# Microcontroller.net
KiCad netlist of a schematic drawn in Altium Designer
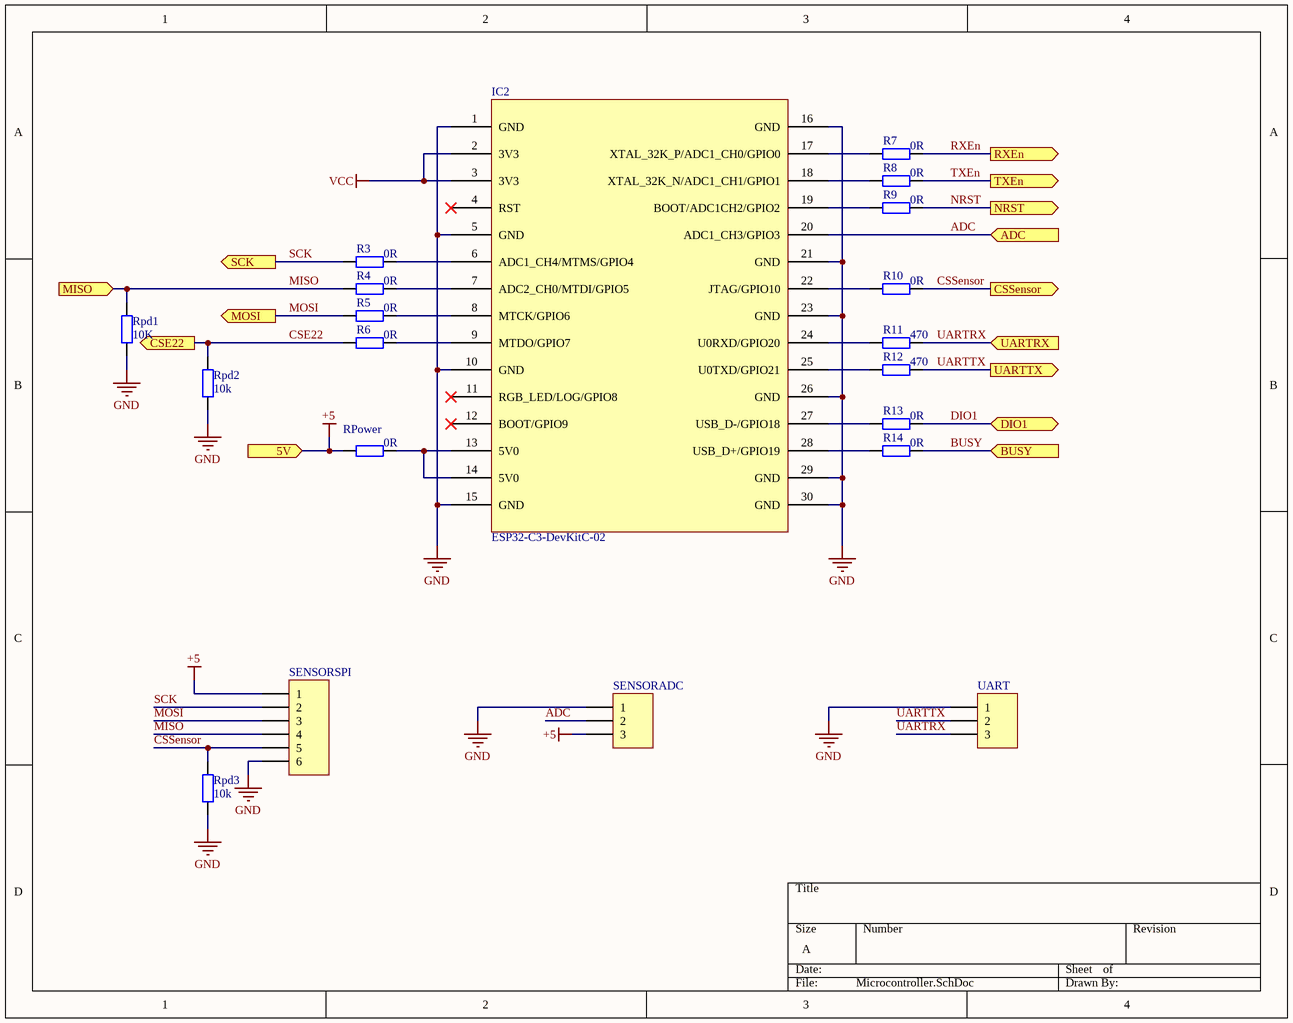
[diagram p0: Microcontroller.SchDoc]

(export (version "E")
  (design (tool "Eeschema 10.0.6"))
  (components
    (comp (ref "IC2")
      (value "ESP32-C3-DevKitC-02")
      (footprint "ESP32-C3-DevKitC-02")
      (libsource (lib "ESP32-C3-DevKitC-02") (part "ESP32-C3-DevKitC-02"))
    )
    (comp (ref "R3")
      (value "0R")
      (footprint "RES0805")
      (description "Resistor")
      (fields
        (field (name "LCSC PART #") "C2074219")
        (field (name "Comment") "Res2")
        (field (name "PUBLISHER") "Altium Limited")
      )
      (libsource (lib "Miscellaneous Devices") (part "Res2"))
    )
    (comp (ref "R4")
      (value "0R")
      (footprint "RES0805")
      (description "Resistor")
      (fields
        (field (name "LCSC PART #") "C2074219")
        (field (name "Comment") "Res2")
        (field (name "PUBLISHER") "Altium Limited")
      )
      (libsource (lib "Miscellaneous Devices") (part "Res2"))
    )
    (comp (ref "R5")
      (value "0R")
      (footprint "RES0805")
      (description "Resistor")
      (fields
        (field (name "LCSC PART #") "C2074219")
        (field (name "Comment") "Res2")
        (field (name "PUBLISHER") "Altium Limited")
      )
      (libsource (lib "Miscellaneous Devices") (part "Res2"))
    )
    (comp (ref "R6")
      (value "0R")
      (footprint "RES0805")
      (description "Resistor")
      (fields
        (field (name "LCSC PART #") "C2074219")
        (field (name "Comment") "Res2")
        (field (name "PUBLISHER") "Altium Limited")
      )
      (libsource (lib "Miscellaneous Devices") (part "Res2"))
    )
    (comp (ref "R7")
      (value "0R")
      (footprint "RES0805")
      (description "Resistor")
      (fields
        (field (name "LCSC PART #") "C2074219")
        (field (name "Comment") "Res2")
        (field (name "PUBLISHER") "Altium Limited")
      )
      (libsource (lib "Miscellaneous Devices") (part "Res2"))
    )
    (comp (ref "R8")
      (value "0R")
      (footprint "RES0805")
      (description "Resistor")
      (fields
        (field (name "LCSC PART #") "C2074219")
        (field (name "Comment") "Res2")
        (field (name "PUBLISHER") "Altium Limited")
      )
      (libsource (lib "Miscellaneous Devices") (part "Res2"))
    )
    (comp (ref "R9")
      (value "0R")
      (footprint "RES0805")
      (description "Resistor")
      (fields
        (field (name "LCSC PART #") "C2074219")
        (field (name "Comment") "Res2")
        (field (name "PUBLISHER") "Altium Limited")
      )
      (libsource (lib "Miscellaneous Devices") (part "Res2"))
    )
    (comp (ref "R10")
      (value "0R")
      (footprint "RES0805")
      (description "Resistor")
      (fields
        (field (name "LCSC PART #") "C2074219")
        (field (name "Comment") "Res2")
        (field (name "PUBLISHER") "Altium Limited")
      )
      (libsource (lib "Miscellaneous Devices") (part "Res2"))
    )
    (comp (ref "R11")
      (value "470")
      (footprint "RES0805")
      (description "Resistor")
      (fields
        (field (name "LCSC PART #") "C2074219")
        (field (name "Comment") "Res2")
        (field (name "PUBLISHER") "Altium Limited")
      )
      (libsource (lib "Miscellaneous Devices") (part "Res2"))
    )
    (comp (ref "R12")
      (value "470")
      (footprint "RES0805")
      (description "Resistor")
      (fields
        (field (name "LCSC PART #") "C2074219")
        (field (name "Comment") "Res2")
        (field (name "PUBLISHER") "Altium Limited")
      )
      (libsource (lib "Miscellaneous Devices") (part "Res2"))
    )
    (comp (ref "R13")
      (value "0R")
      (footprint "RES0805")
      (description "Resistor")
      (fields
        (field (name "LCSC PART #") "C2074219")
        (field (name "Comment") "Res2")
        (field (name "PUBLISHER") "Altium Limited")
      )
      (libsource (lib "Miscellaneous Devices") (part "Res2"))
    )
    (comp (ref "R14")
      (value "0R")
      (footprint "RES0805")
      (description "Resistor")
      (fields
        (field (name "LCSC PART #") "C2074219")
        (field (name "Comment") "Res2")
        (field (name "PUBLISHER") "Altium Limited")
      )
      (libsource (lib "Miscellaneous Devices") (part "Res2"))
    )
    (comp (ref "Rpd1")
      (value "10K")
      (footprint "RES0805")
      (description "Resistor")
      (fields
        (field (name "LCSC PART #") "C2074219")
        (field (name "Comment") "Res2")
        (field (name "PUBLISHER") "Altium Limited")
      )
      (libsource (lib "") (part "Res2_1"))
    )
    (comp (ref "Rpd2")
      (value "10k")
      (footprint "RES0805")
      (description "Resistor")
      (fields
        (field (name "LCSC PART #") "C2074219")
        (field (name "Comment") "Res2")
        (field (name "PUBLISHER") "Altium Limited")
      )
      (libsource (lib "") (part "Res2_1"))
    )
    (comp (ref "Rpd3")
      (value "10k")
      (footprint "RES0805")
      (description "Resistor")
      (fields
        (field (name "LCSC PART #") "C2074219")
        (field (name "Comment") "Res2")
        (field (name "PUBLISHER") "Altium Limited")
      )
      (libsource (lib "") (part "Res2_1"))
    )
    (comp (ref "RPower")
      (value "0R")
      (footprint "RES0805")
      (description "Resistor")
      (fields
        (field (name "LCSC PART #") "C2074219")
        (field (name "Comment") "Res2")
        (field (name "PUBLISHER") "Altium Limited")
      )
      (libsource (lib "Miscellaneous Devices") (part "Res2"))
    )
    (comp (ref "SENSORADC")
      (value "Header 3")
      (footprint "Conn 1x3P")
      (description "Header, 3-Pin")
      (fields (field (name "PUBLISHER") "Altium Limited"))
      (libsource (lib "Miscellaneous Connectors") (part "Header 3"))
    )
    (comp (ref "SENSORSPI")
      (value "Header 6")
      (footprint "Conn 1x6P")
      (description "Header, 6-Pin")
      (fields (field (name "PUBLISHER") "Altium Limited"))
      (libsource (lib "Miscellaneous Connectors") (part "Header 6"))
    )
    (comp (ref "UART")
      (value "Header 3")
      (footprint "Conn 1x3P")
      (description "Header, 3-Pin")
      (fields (field (name "PUBLISHER") "Altium Limited"))
      (libsource (lib "Miscellaneous Connectors") (part "Header 3"))
    )
  )
  (nets
    (net (code "1") (name "+5") (class "Default")
      (node (ref "RPower") (pin "1") (pinfunction "1_1") (pintype "passive"))
      (node (ref "SENSORADC") (pin "3") (pinfunction "3_3") (pintype "passive"))
      (node (ref "SENSORSPI") (pin "1") (pinfunction "1_1") (pintype "passive"))
    )
    (net (code "2") (name "/ADC") (class "Default")
      (node (ref "IC2") (pin "20") (pinfunction "ADC1_CH3/GPIO3_20") (pintype "passive"))
      (node (ref "SENSORADC") (pin "2") (pinfunction "2_2") (pintype "passive"))
    )
    (net (code "3") (name "/BUSY") (class "Default")
      (node (ref "R14") (pin "2") (pinfunction "2_2") (pintype "passive"))
    )
    (net (code "4") (name "/CSE22") (class "Default")
      (node (ref "R6") (pin "1") (pinfunction "1_1") (pintype "passive"))
      (node (ref "Rpd2") (pin "2") (pinfunction "2_2") (pintype "passive"))
    )
    (net (code "5") (name "/CSSensor") (class "Default")
      (node (ref "R10") (pin "2") (pinfunction "2_2") (pintype "passive"))
      (node (ref "Rpd3") (pin "2") (pinfunction "2_2") (pintype "passive"))
      (node (ref "SENSORSPI") (pin "5") (pinfunction "5_5") (pintype "passive"))
    )
    (net (code "6") (name "/DIO1") (class "Default")
      (node (ref "R13") (pin "2") (pinfunction "2_2") (pintype "passive"))
    )
    (net (code "7") (name "/MISO") (class "Default")
      (node (ref "R4") (pin "1") (pinfunction "1_1") (pintype "passive"))
      (node (ref "Rpd1") (pin "2") (pinfunction "2_2") (pintype "passive"))
      (node (ref "SENSORSPI") (pin "4") (pinfunction "4_4") (pintype "passive"))
    )
    (net (code "8") (name "/MOSI") (class "Default")
      (node (ref "R5") (pin "1") (pinfunction "1_1") (pintype "passive"))
      (node (ref "SENSORSPI") (pin "3") (pinfunction "3_3") (pintype "passive"))
    )
    (net (code "9") (name "/NRST") (class "Default")
      (node (ref "R9") (pin "2") (pinfunction "2_2") (pintype "passive"))
    )
    (net (code "10") (name "/RXEn") (class "Default")
      (node (ref "R7") (pin "2") (pinfunction "2_2") (pintype "passive"))
    )
    (net (code "11") (name "/SCK") (class "Default")
      (node (ref "R3") (pin "1") (pinfunction "1_1") (pintype "passive"))
      (node (ref "SENSORSPI") (pin "2") (pinfunction "2_2") (pintype "passive"))
    )
    (net (code "12") (name "/TXEn") (class "Default")
      (node (ref "R8") (pin "2") (pinfunction "2_2") (pintype "passive"))
    )
    (net (code "13") (name "/UARTRX") (class "Default")
      (node (ref "R11") (pin "2") (pinfunction "2_2") (pintype "passive"))
      (node (ref "UART") (pin "3") (pinfunction "3_3") (pintype "passive"))
    )
    (net (code "14") (name "/UARTTX") (class "Default")
      (node (ref "R12") (pin "2") (pinfunction "2_2") (pintype "passive"))
      (node (ref "UART") (pin "2") (pinfunction "2_2") (pintype "passive"))
    )
    (net (code "15") (name "GND") (class "Default")
      (node (ref "IC2") (pin "1") (pinfunction "GND_1") (pintype "passive"))
      (node (ref "IC2") (pin "10") (pinfunction "GND_10") (pintype "passive"))
      (node (ref "IC2") (pin "15") (pinfunction "GND_15") (pintype "passive"))
      (node (ref "IC2") (pin "16") (pinfunction "GND_16") (pintype "passive"))
      (node (ref "IC2") (pin "21") (pinfunction "GND_21") (pintype "passive"))
      (node (ref "IC2") (pin "23") (pinfunction "GND_23") (pintype "passive"))
      (node (ref "IC2") (pin "26") (pinfunction "GND_26") (pintype "passive"))
      (node (ref "IC2") (pin "29") (pinfunction "GND_29") (pintype "passive"))
      (node (ref "IC2") (pin "30") (pinfunction "GND_30") (pintype "passive"))
      (node (ref "IC2") (pin "5") (pinfunction "GND_5") (pintype "passive"))
      (node (ref "Rpd1") (pin "1") (pinfunction "1_1") (pintype "passive"))
      (node (ref "Rpd2") (pin "1") (pinfunction "1_1") (pintype "passive"))
      (node (ref "Rpd3") (pin "1") (pinfunction "1_1") (pintype "passive"))
      (node (ref "SENSORADC") (pin "1") (pinfunction "1_1") (pintype "passive"))
      (node (ref "SENSORSPI") (pin "6") (pinfunction "6_6") (pintype "passive"))
      (node (ref "UART") (pin "1") (pinfunction "1_1") (pintype "passive"))
    )
    (net (code "16") (name "Net-(IC2-5V0-Pad13)") (class "Default")
      (node (ref "IC2") (pin "13") (pinfunction "5V0_13") (pintype "passive"))
      (node (ref "IC2") (pin "14") (pinfunction "5V0_14") (pintype "passive"))
      (node (ref "RPower") (pin "2") (pinfunction "2_2") (pintype "passive"))
    )
    (net (code "17") (name "Net-(IC2-ADC1_CH4{slash}MTMS{slash}GPIO4)") (class "Default")
      (node (ref "IC2") (pin "6") (pinfunction "ADC1_CH4/MTMS/GPIO4_6") (pintype "passive"))
      (node (ref "R3") (pin "2") (pinfunction "2_2") (pintype "passive"))
    )
    (net (code "18") (name "Net-(IC2-ADC2_CH0{slash}MTDI{slash}GPIO5)") (class "Default")
      (node (ref "IC2") (pin "7") (pinfunction "ADC2_CH0/MTDI/GPIO5_7") (pintype "passive"))
      (node (ref "R4") (pin "2") (pinfunction "2_2") (pintype "passive"))
    )
    (net (code "19") (name "Net-(IC2-BOOT{slash}ADC1CH2{slash}GPIO2)") (class "Default")
      (node (ref "IC2") (pin "19") (pinfunction "BOOT/ADC1CH2/GPIO2_19") (pintype "passive"))
      (node (ref "R9") (pin "1") (pinfunction "1_1") (pintype "passive"))
    )
    (net (code "20") (name "Net-(IC2-JTAG{slash}GPIO10)") (class "Default")
      (node (ref "IC2") (pin "22") (pinfunction "JTAG/GPIO10_22") (pintype "passive"))
      (node (ref "R10") (pin "1") (pinfunction "1_1") (pintype "passive"))
    )
    (net (code "21") (name "Net-(IC2-MTCK{slash}GPIO6)") (class "Default")
      (node (ref "IC2") (pin "8") (pinfunction "MTCK/GPIO6_8") (pintype "passive"))
      (node (ref "R5") (pin "2") (pinfunction "2_2") (pintype "passive"))
    )
    (net (code "22") (name "Net-(IC2-MTDO{slash}GPIO7)") (class "Default")
      (node (ref "IC2") (pin "9") (pinfunction "MTDO/GPIO7_9") (pintype "passive"))
      (node (ref "R6") (pin "2") (pinfunction "2_2") (pintype "passive"))
    )
    (net (code "23") (name "Net-(IC2-U0RXD{slash}GPIO20)") (class "Default")
      (node (ref "IC2") (pin "24") (pinfunction "U0RXD/GPIO20_24") (pintype "passive"))
      (node (ref "R11") (pin "1") (pinfunction "1_1") (pintype "passive"))
    )
    (net (code "24") (name "Net-(IC2-U0TXD{slash}GPIO21)") (class "Default")
      (node (ref "IC2") (pin "25") (pinfunction "U0TXD/GPIO21_25") (pintype "passive"))
      (node (ref "R12") (pin "1") (pinfunction "1_1") (pintype "passive"))
    )
    (net (code "25") (name "Net-(IC2-USB_D+{slash}GPIO19)") (class "Default")
      (node (ref "IC2") (pin "28") (pinfunction "USB_D+/GPIO19_28") (pintype "passive"))
      (node (ref "R14") (pin "1") (pinfunction "1_1") (pintype "passive"))
    )
    (net (code "26") (name "Net-(IC2-USB_D-{slash}GPIO18)") (class "Default")
      (node (ref "IC2") (pin "27") (pinfunction "USB_D-/GPIO18_27") (pintype "passive"))
      (node (ref "R13") (pin "1") (pinfunction "1_1") (pintype "passive"))
    )
    (net (code "27") (name "Net-(IC2-XTAL_32K_N{slash}ADC1_CH1{slash}GPIO1)") (class "Default")
      (node (ref "IC2") (pin "18") (pinfunction "XTAL_32K_N/ADC1_CH1/GPIO1_18") (pintype "passive"))
      (node (ref "R8") (pin "1") (pinfunction "1_1") (pintype "passive"))
    )
    (net (code "28") (name "Net-(IC2-XTAL_32K_P{slash}ADC1_CH0{slash}GPIO0)") (class "Default")
      (node (ref "IC2") (pin "17") (pinfunction "XTAL_32K_P/ADC1_CH0/GPIO0_17") (pintype "passive"))
      (node (ref "R7") (pin "1") (pinfunction "1_1") (pintype "passive"))
    )
    (net (code "29") (name "VCC") (class "Default")
      (node (ref "IC2") (pin "2") (pinfunction "3V3_2") (pintype "passive"))
      (node (ref "IC2") (pin "3") (pinfunction "3V3_3") (pintype "passive"))
    )
    (net (code "30") (name "unconnected-(IC2-BOOT{slash}GPIO9-Pad12)") (class "Default")
      (node (ref "IC2") (pin "12") (pinfunction "BOOT/GPIO9_12") (pintype "passive+no_connect"))
    )
    (net (code "31") (name "unconnected-(IC2-RGB_LED{slash}LOG{slash}GPIO8-Pad11)") (class "Default")
      (node (ref "IC2") (pin "11") (pinfunction "RGB_LED/LOG/GPIO8_11") (pintype "passive+no_connect"))
    )
    (net (code "32") (name "unconnected-(IC2-RST-Pad4)") (class "Default")
      (node (ref "IC2") (pin "4") (pinfunction "RST_4") (pintype "passive+no_connect"))
    )
  )
)
